# BalanceCarCircuit.net
KiCad netlist of a schematic drawn in Altium Designer
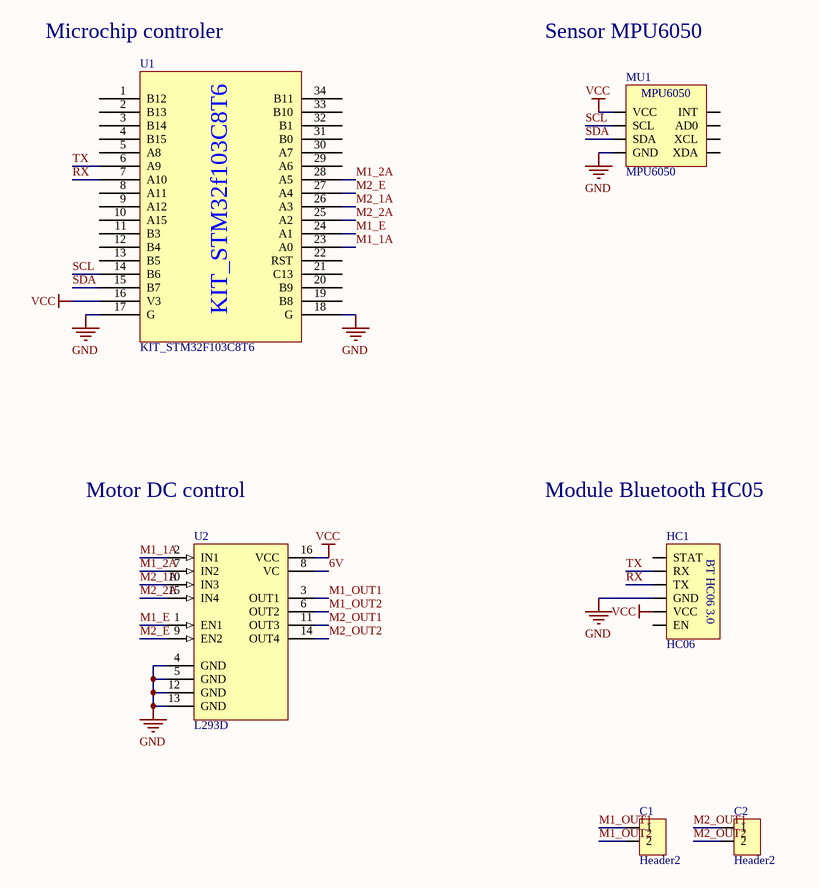
[diagram p0: BalanceCarCircuit.SchDoc]

(export (version "E")
  (design (tool "Eeschema 10.0.6"))
  (components
    (comp (ref "C1")
      (value "Header2")
      (footprint "Header2")
      (description "Header IDC, 2 x 1 Pin Vertical 2.54mm Pitch (Non-Boxed, Male)")
      (fields
        (field (name "MANUFACTURER") "Würth Elektronik eiSos GmbH")
        (field (name "PARTNO") "613002143121")
        (field (name "CREATED BY") "Karrer Zheng")
      )
      (libsource (lib "LIBRARY") (part "Header2"))
    )
    (comp (ref "C2")
      (value "Header2")
      (footprint "Header2")
      (description "Header IDC, 2 x 1 Pin Vertical 2.54mm Pitch (Non-Boxed, Male)")
      (fields
        (field (name "MANUFACTURER") "Würth Elektronik eiSos GmbH")
        (field (name "PARTNO") "613002143121")
        (field (name "CREATED BY") "Karrer Zheng")
      )
      (libsource (lib "LIBRARY") (part "Header2"))
    )
    (comp (ref "HC1")
      (value "HC06")
      (footprint "HC06")
      (fields
        (field (name "MANUFACTURER") "Würth Elektronik eiSos GmbH")
        (field (name "PARTNO") "613004143121")
        (field (name "CREATED BY") "Karrer Zheng")
      )
      (libsource (lib "LIBRARY") (part "HC06"))
    )
    (comp (ref "MU1")
      (value "MPU6050")
      (footprint "MPU6050")
      (fields
        (field (name "MANUFACTURER") "Würth Elektronik eiSos GmbH")
        (field (name "PARTNO") "613004143121")
        (field (name "CREATED BY") "Karrer Zheng")
      )
      (libsource (lib "LIBRARY") (part "MPU6050"))
    )
    (comp (ref "U1")
      (value "KIT_STM32F103C8T6")
      (footprint "DIP_KIT_STM32F103C8T6 - duplicate")
      (description "KIT STM32F103C8T6")
      (libsource (lib "UnitLibrary") (part "KIT_STM32F103C8T6"))
    )
    (comp (ref "U2")
      (value "L293D")
      (footprint "DIP16")
      (description "Push-Pull Four Channel Driver With Diode")
      (fields (field (name "PUBLISHER") "Altium Limited"))
      (libsource (lib "LIBRARY") (part "L293D"))
    )
  )
  (nets
    (net (code "1") (name "/6V") (class "Default")
      (node (ref "U2") (pin "8") (pinfunction "VC_8") (pintype "power_in"))
    )
    (net (code "2") (name "/M1_1A") (class "Default")
      (node (ref "U1") (pin "23") (pinfunction "A0_23") (pintype "passive"))
      (node (ref "U2") (pin "2") (pinfunction "IN1_2") (pintype "input"))
    )
    (net (code "3") (name "/M1_2A") (class "Default")
      (node (ref "U1") (pin "28") (pinfunction "A5_28") (pintype "passive"))
      (node (ref "U2") (pin "7") (pinfunction "IN2_7") (pintype "input"))
    )
    (net (code "4") (name "/M1_E") (class "Default")
      (node (ref "U1") (pin "24") (pinfunction "A1_24") (pintype "passive"))
      (node (ref "U2") (pin "1") (pinfunction "EN1_1") (pintype "input"))
    )
    (net (code "5") (name "/M1_OUT1") (class "Default")
      (node (ref "C1") (pin "1") (pinfunction "1_1") (pintype "passive"))
      (node (ref "U2") (pin "3") (pinfunction "OUT1_3") (pintype "tri_state"))
    )
    (net (code "6") (name "/M1_OUT2") (class "Default")
      (node (ref "C1") (pin "2") (pinfunction "2_2") (pintype "passive"))
      (node (ref "U2") (pin "6") (pinfunction "OUT2_6") (pintype "tri_state"))
    )
    (net (code "7") (name "/M2_1A") (class "Default")
      (node (ref "U1") (pin "26") (pinfunction "A3_26") (pintype "passive"))
      (node (ref "U2") (pin "10") (pinfunction "IN3_10") (pintype "input"))
    )
    (net (code "8") (name "/M2_2A") (class "Default")
      (node (ref "U1") (pin "25") (pinfunction "A2_25") (pintype "passive"))
      (node (ref "U2") (pin "15") (pinfunction "IN4_15") (pintype "input"))
    )
    (net (code "9") (name "/M2_E") (class "Default")
      (node (ref "U1") (pin "27") (pinfunction "A4_27") (pintype "passive"))
      (node (ref "U2") (pin "9") (pinfunction "EN2_9") (pintype "input"))
    )
    (net (code "10") (name "/M2_OUT1") (class "Default")
      (node (ref "C2") (pin "1") (pinfunction "1_1") (pintype "passive"))
      (node (ref "U2") (pin "11") (pinfunction "OUT3_11") (pintype "tri_state"))
    )
    (net (code "11") (name "/M2_OUT2") (class "Default")
      (node (ref "C2") (pin "2") (pinfunction "2_2") (pintype "passive"))
      (node (ref "U2") (pin "14") (pinfunction "OUT4_14") (pintype "tri_state"))
    )
    (net (code "12") (name "/RX") (class "Default")
      (node (ref "HC1") (pin "3") (pinfunction "TX_3") (pintype "passive"))
      (node (ref "U1") (pin "7") (pinfunction "A10_7") (pintype "passive"))
    )
    (net (code "13") (name "/SCL") (class "Default")
      (node (ref "MU1") (pin "3") (pinfunction "SCL_3") (pintype "passive"))
      (node (ref "U1") (pin "14") (pinfunction "B6_14") (pintype "passive"))
    )
    (net (code "14") (name "/SDA") (class "Default")
      (node (ref "MU1") (pin "4") (pinfunction "SDA_4") (pintype "passive"))
      (node (ref "U1") (pin "15") (pinfunction "B7_15") (pintype "passive"))
    )
    (net (code "15") (name "/TX") (class "Default")
      (node (ref "HC1") (pin "2") (pinfunction "RX_2") (pintype "passive"))
      (node (ref "U1") (pin "6") (pinfunction "A9_6") (pintype "passive"))
    )
    (net (code "16") (name "GND") (class "Default")
      (node (ref "HC1") (pin "4") (pinfunction "GND_4") (pintype "passive"))
      (node (ref "MU1") (pin "2") (pinfunction "GND_2") (pintype "passive"))
      (node (ref "U1") (pin "17") (pinfunction "G_17") (pintype "passive"))
      (node (ref "U1") (pin "18") (pinfunction "G_18") (pintype "passive"))
      (node (ref "U2") (pin "12") (pinfunction "GND_12") (pintype "power_in"))
      (node (ref "U2") (pin "13") (pinfunction "GND_13") (pintype "power_in"))
      (node (ref "U2") (pin "4") (pinfunction "GND_4") (pintype "power_in"))
      (node (ref "U2") (pin "5") (pinfunction "GND_5") (pintype "power_in"))
    )
    (net (code "17") (name "VCC") (class "Default")
      (node (ref "HC1") (pin "5") (pinfunction "VCC_5") (pintype "passive"))
      (node (ref "MU1") (pin "1") (pinfunction "VCC_1") (pintype "passive"))
      (node (ref "U1") (pin "16") (pinfunction "V3_16") (pintype "passive"))
      (node (ref "U2") (pin "16") (pinfunction "VCC_16") (pintype "power_in"))
    )
    (net (code "18") (name "unconnected-(HC1-EN-Pad6)") (class "Default")
      (node (ref "HC1") (pin "6") (pinfunction "EN_6") (pintype "passive"))
    )
    (net (code "19") (name "unconnected-(HC1-STAT-Pad1)") (class "Default")
      (node (ref "HC1") (pin "1") (pinfunction "STAT_1") (pintype "passive"))
    )
    (net (code "20") (name "unconnected-(MU1-AD0-Pad7)") (class "Default")
      (node (ref "MU1") (pin "7") (pinfunction "AD0_7") (pintype "passive"))
    )
    (net (code "21") (name "unconnected-(MU1-INT-Pad8)") (class "Default")
      (node (ref "MU1") (pin "8") (pinfunction "INT_8") (pintype "passive"))
    )
    (net (code "22") (name "unconnected-(MU1-XCL-Pad6)") (class "Default")
      (node (ref "MU1") (pin "6") (pinfunction "XCL_6") (pintype "passive"))
    )
    (net (code "23") (name "unconnected-(MU1-XDA-Pad5)") (class "Default")
      (node (ref "MU1") (pin "5") (pinfunction "XDA_5") (pintype "passive"))
    )
    (net (code "24") (name "unconnected-(U1-A6-Pad29)") (class "Default")
      (node (ref "U1") (pin "29") (pinfunction "A6_29") (pintype "passive"))
    )
    (net (code "25") (name "unconnected-(U1-A7-Pad30)") (class "Default")
      (node (ref "U1") (pin "30") (pinfunction "A7_30") (pintype "passive"))
    )
    (net (code "26") (name "unconnected-(U1-A8-Pad5)") (class "Default")
      (node (ref "U1") (pin "5") (pinfunction "A8_5") (pintype "passive"))
    )
    (net (code "27") (name "unconnected-(U1-A11-Pad8)") (class "Default")
      (node (ref "U1") (pin "8") (pinfunction "A11_8") (pintype "passive"))
    )
    (net (code "28") (name "unconnected-(U1-A12-Pad9)") (class "Default")
      (node (ref "U1") (pin "9") (pinfunction "A12_9") (pintype "passive"))
    )
    (net (code "29") (name "unconnected-(U1-A15-Pad10)") (class "Default")
      (node (ref "U1") (pin "10") (pinfunction "A15_10") (pintype "passive"))
    )
    (net (code "30") (name "unconnected-(U1-B0-Pad31)") (class "Default")
      (node (ref "U1") (pin "31") (pinfunction "B0_31") (pintype "passive"))
    )
    (net (code "31") (name "unconnected-(U1-B1-Pad32)") (class "Default")
      (node (ref "U1") (pin "32") (pinfunction "B1_32") (pintype "passive"))
    )
    (net (code "32") (name "unconnected-(U1-B3-Pad11)") (class "Default")
      (node (ref "U1") (pin "11") (pinfunction "B3_11") (pintype "passive"))
    )
    (net (code "33") (name "unconnected-(U1-B4-Pad12)") (class "Default")
      (node (ref "U1") (pin "12") (pinfunction "B4_12") (pintype "passive"))
    )
    (net (code "34") (name "unconnected-(U1-B5-Pad13)") (class "Default")
      (node (ref "U1") (pin "13") (pinfunction "B5_13") (pintype "passive"))
    )
    (net (code "35") (name "unconnected-(U1-B8-Pad19)") (class "Default")
      (node (ref "U1") (pin "19") (pinfunction "B8_19") (pintype "passive"))
    )
    (net (code "36") (name "unconnected-(U1-B9-Pad20)") (class "Default")
      (node (ref "U1") (pin "20") (pinfunction "B9_20") (pintype "passive"))
    )
    (net (code "37") (name "unconnected-(U1-B10-Pad33)") (class "Default")
      (node (ref "U1") (pin "33") (pinfunction "B10_33") (pintype "passive"))
    )
    (net (code "38") (name "unconnected-(U1-B11-Pad34)") (class "Default")
      (node (ref "U1") (pin "34") (pinfunction "B11_34") (pintype "passive"))
    )
    (net (code "39") (name "unconnected-(U1-B12-Pad1)") (class "Default")
      (node (ref "U1") (pin "1") (pinfunction "B12_1") (pintype "passive"))
    )
    (net (code "40") (name "unconnected-(U1-B13-Pad2)") (class "Default")
      (node (ref "U1") (pin "2") (pinfunction "B13_2") (pintype "passive"))
    )
    (net (code "41") (name "unconnected-(U1-B14-Pad3)") (class "Default")
      (node (ref "U1") (pin "3") (pinfunction "B14_3") (pintype "passive"))
    )
    (net (code "42") (name "unconnected-(U1-B15-Pad4)") (class "Default")
      (node (ref "U1") (pin "4") (pinfunction "B15_4") (pintype "passive"))
    )
    (net (code "43") (name "unconnected-(U1-C13-Pad21)") (class "Default")
      (node (ref "U1") (pin "21") (pinfunction "C13_21") (pintype "passive"))
    )
    (net (code "44") (name "unconnected-(U1-RST-Pad22)") (class "Default")
      (node (ref "U1") (pin "22") (pinfunction "RST_22") (pintype "passive"))
    )
  )
)
